# front_end_mk1.net
KiCad netlist of a schematic drawn in EAGLE
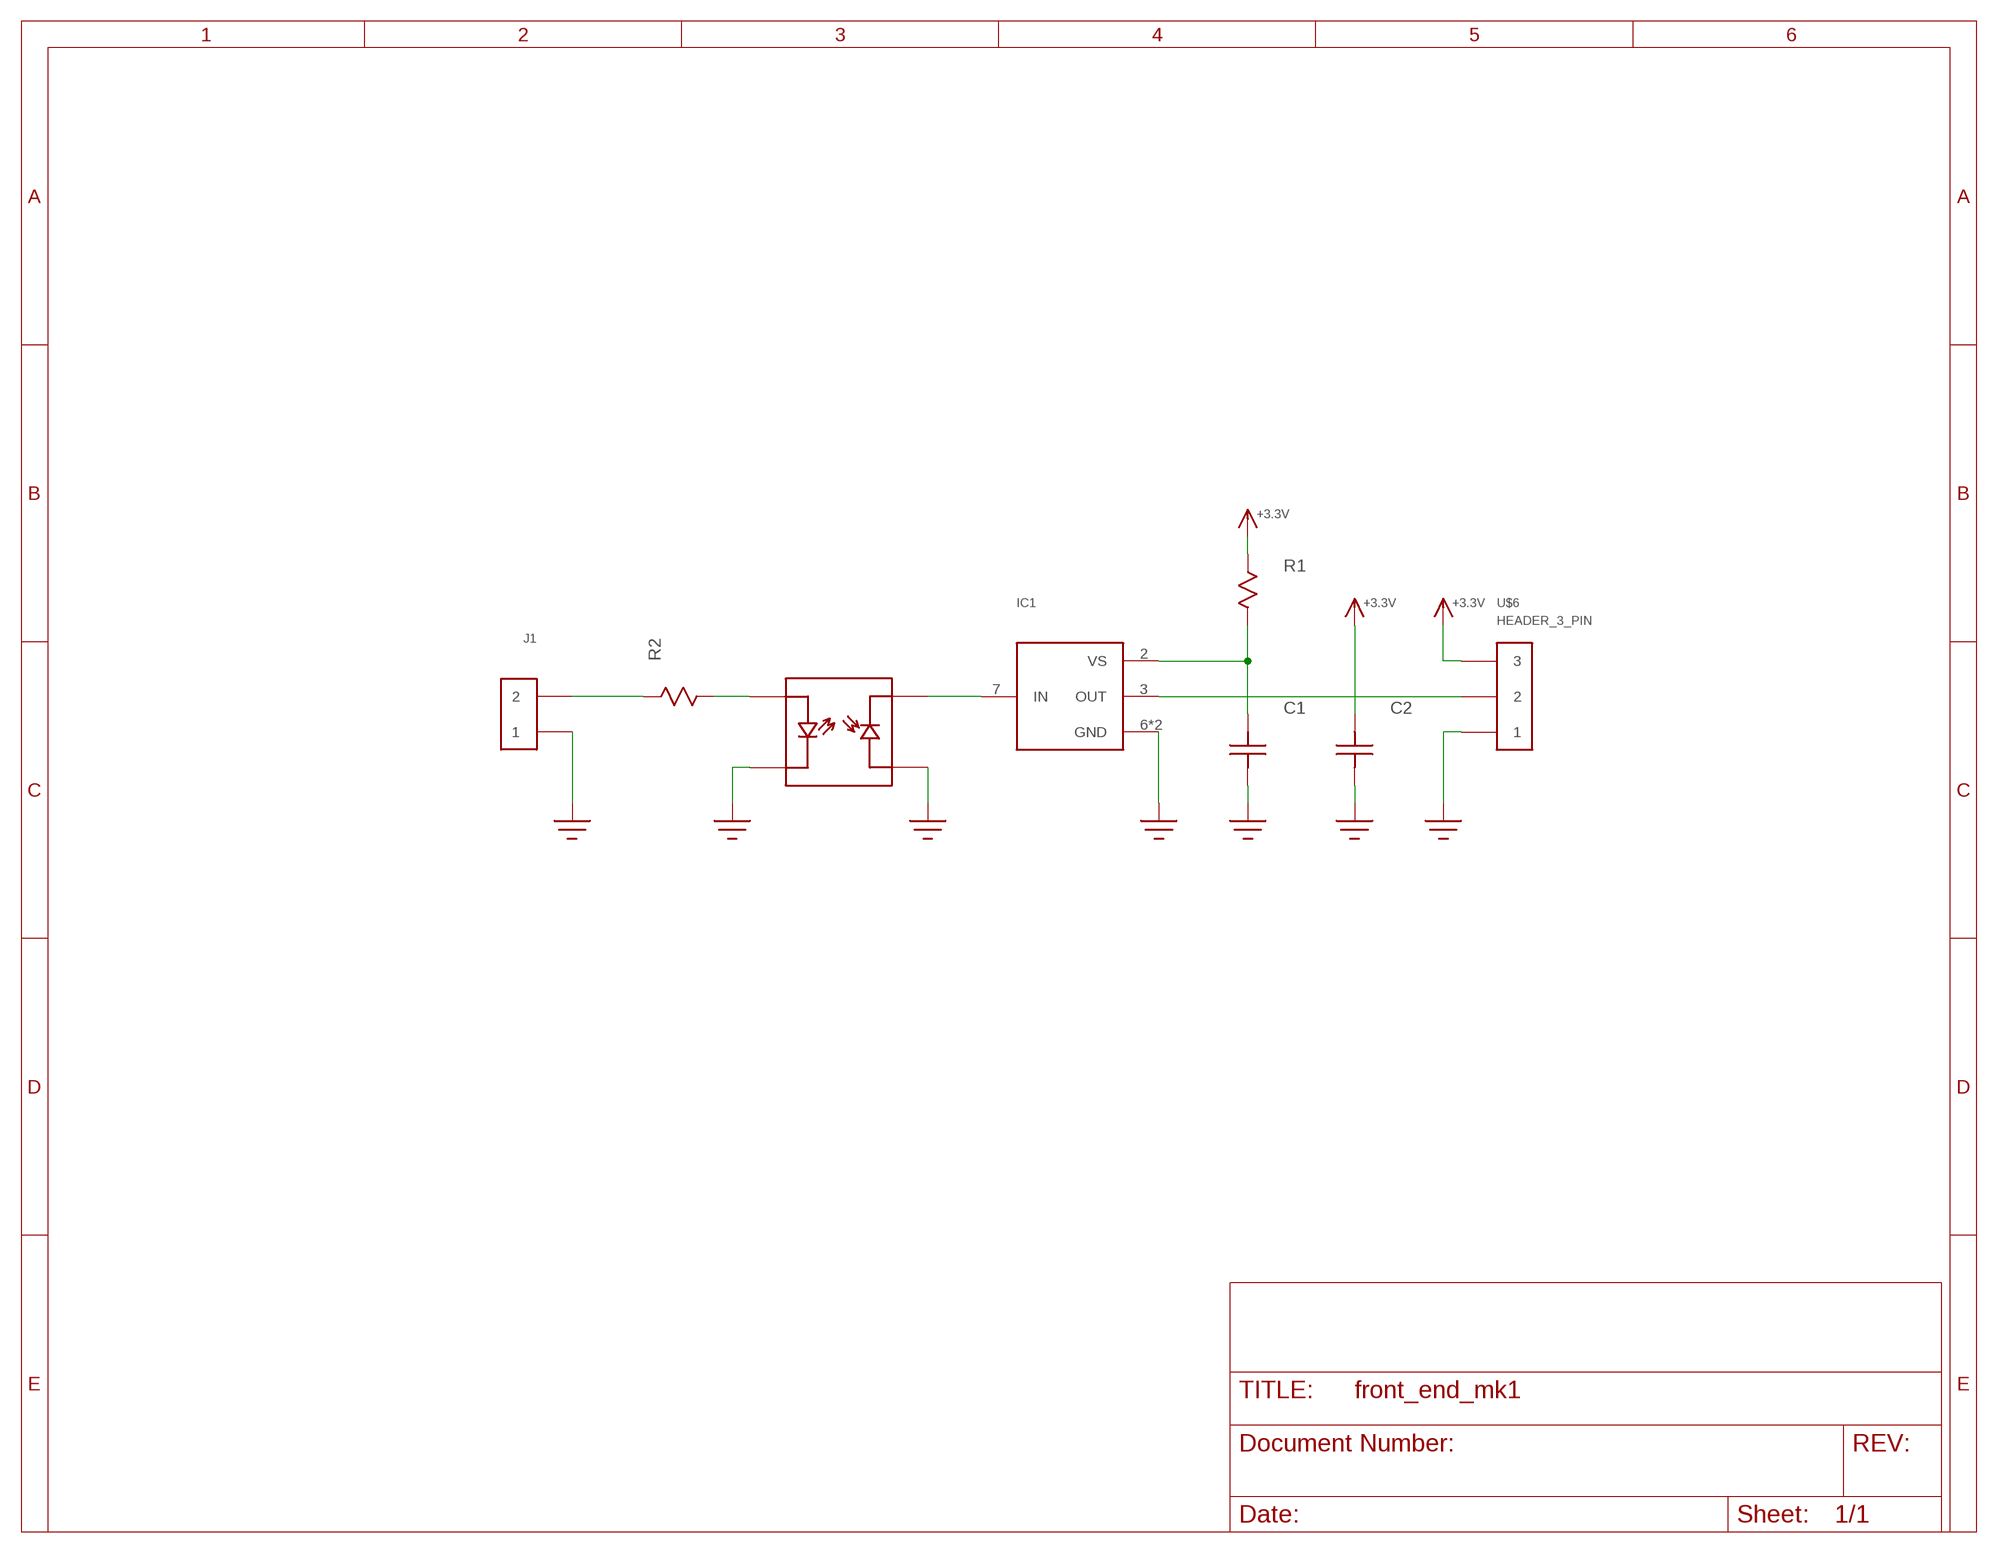
[diagram p0: schematic, sheet 1]

(export (version "E")
  (design (tool "Eeschema 10.0.6"))
  (components
    (comp (ref "C1")
      (value "C0603")
      (footprint "eagle-import:C0603")
      (libsource (lib "eagle-import") (part "C0603"))
    )
    (comp (ref "C2")
      (value "C0805")
      (footprint "eagle-import:0805")
      (libsource (lib "eagle-import") (part "C0805"))
    )
    (comp (ref "IC1")
      (value "VSOP98260")
      (footprint "eagle-import:VSOP98260")
      (libsource (lib "eagle-import") (part "VSOP98260"))
    )
    (comp (ref "IC2")
      (value "HSDL-9100")
      (footprint "eagle-import:HDSL-9100")
      (libsource (lib "eagle-import") (part "HSDL-9100"))
    )
    (comp (ref "J1")
      (value "HEADER_2_PIN")
      (footprint "eagle-import:HEADER_2_PIN")
      (libsource (lib "eagle-import") (part "HEADER_2_PIN"))
    )
    (comp (ref "R1")
      (value "R0603")
      (footprint "eagle-import:R0603")
      (libsource (lib "eagle-import") (part "R0603"))
    )
    (comp (ref "R2")
      (value "R1206")
      (footprint "eagle-import:R1206")
      (libsource (lib "eagle-import") (part "R1206"))
    )
    (comp (ref "U$6")
      (value "HEADER_3_PIN")
      (footprint "eagle-import:HEADER_3_PIN")
      (libsource (lib "eagle-import") (part "HEADER_3_PIN"))
    )
  )
  (nets
    (net (code "1") (name "+3.3V") (class "Default")
      (node (ref "C2") (pin "P$2") (pinfunction "P$2_P$2") (pintype "bidirectional"))
      (node (ref "R1") (pin "P$1") (pinfunction "P$3_P$1") (pintype "bidirectional"))
      (node (ref "U$6") (pin "3") (pinfunction "3_3") (pintype "bidirectional"))
    )
    (net (code "2") (name "GND") (class "Default")
      (node (ref "C1") (pin "P$1") (pinfunction "P$1_P$1") (pintype "bidirectional"))
      (node (ref "C2") (pin "P$1") (pinfunction "P$1_P$1") (pintype "bidirectional"))
      (node (ref "IC1") (pin "6") (pinfunction "GND_6") (pintype "bidirectional"))
      (node (ref "IC1") (pin "8") (pinfunction "GND_8") (pintype "bidirectional"))
      (node (ref "IC2") (pin "2") (pinfunction "LED_CATHODE_2") (pintype "bidirectional"))
      (node (ref "IC2") (pin "3") (pinfunction "PHOTODIODE_ANODE_3") (pintype "bidirectional"))
      (node (ref "J1") (pin "1") (pinfunction "1_1") (pintype "bidirectional"))
      (node (ref "U$6") (pin "1") (pinfunction "1_1") (pintype "bidirectional"))
    )
    (net (code "3") (name "Net-(IC1-IN)") (class "Default")
      (node (ref "IC1") (pin "7") (pinfunction "IN_7") (pintype "bidirectional"))
      (node (ref "IC2") (pin "4") (pinfunction "PHOTODIODE_CATHODE_4") (pintype "bidirectional"))
    )
    (net (code "4") (name "Net-(IC1-OUT)") (class "Default")
      (node (ref "IC1") (pin "3") (pinfunction "OUT_3") (pintype "bidirectional"))
      (node (ref "U$6") (pin "2") (pinfunction "2_2") (pintype "bidirectional"))
    )
    (net (code "5") (name "Net-(IC1-VS)") (class "Default")
      (node (ref "C1") (pin "P$2") (pinfunction "P$2_P$2") (pintype "bidirectional"))
      (node (ref "IC1") (pin "2") (pinfunction "VS_2") (pintype "bidirectional"))
      (node (ref "R1") (pin "P$2") (pinfunction "P$4_P$2") (pintype "bidirectional"))
    )
    (net (code "6") (name "Net-(IC2-LED_ANODE)") (class "Default")
      (node (ref "IC2") (pin "1") (pinfunction "LED_ANODE_1") (pintype "bidirectional"))
      (node (ref "R2") (pin "P$2") (pinfunction "P$4_P$2") (pintype "bidirectional"))
    )
    (net (code "7") (name "Net-(R2-P$3)") (class "Default")
      (node (ref "J1") (pin "2") (pinfunction "2_2") (pintype "bidirectional"))
      (node (ref "R2") (pin "P$1") (pinfunction "P$3_P$1") (pintype "bidirectional"))
    )
  )
)
